# 02_POWER.net
KiCad netlist of a schematic drawn in Altium Designer
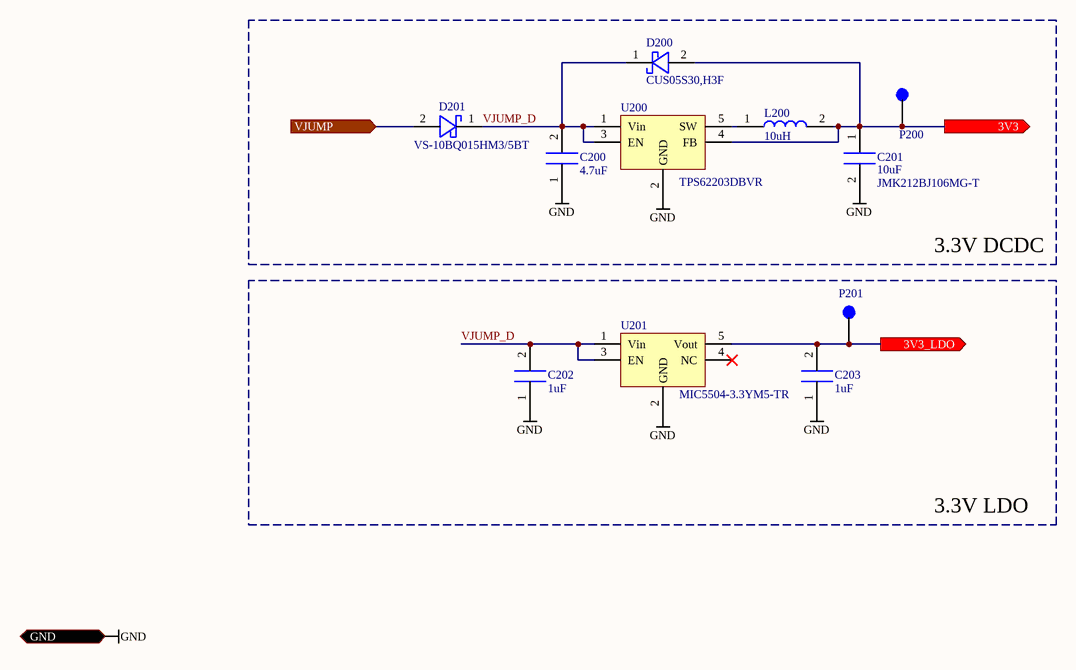
[diagram p0: 02_POWER.SchDoc]

(export (version "E")
  (design (tool "Eeschema 10.0.6"))
  (components
    (comp (ref "C200")
      (value "4.7uF")
      (footprint "CAP_0805")
      (description "CAP 4.7uF 10% 16V 0805 X7R")
      (fields (field (name "TOLERANCE") "10%") (field (name "MANUFACTURER") "MURATA"))
      (libsource (lib "Capacitors") (part "4.7uF_10%_16V_0805_X7R_GRM21BR71C475KE51L"))
    )
    (comp (ref "C201")
      (value "10uF")
      (footprint "CAP_0805")
      (description "CAP 10uF 20% 6.3V 0805 X5R")
      (fields
        (field (name "TOLERANCE") "20%")
        (field (name "MANUFACTURER") "TAYIO YUDEN")
        (field (name "MANUFACTURER REFERENCE") "JMK212BJ106MG-T")
      )
      (libsource (lib "Capacitors") (part "10uF_20%_6.3V_0805_X5R_JMK212BJ106MG-T"))
    )
    (comp (ref "C202")
      (value "1uF")
      (footprint "CAP_0402")
      (description "CAPACITOR 1uF 10% X5R 0402")
      (fields (field (name "TOLERANCE") "10%") (field (name "MANUFACTURER") "MURATA"))
      (libsource (lib "Capacitors") (part "1uF_10%_35V_0402_GRM155R6YA105KE11J"))
    )
    (comp (ref "C203")
      (value "1uF")
      (footprint "CAP_0402")
      (description "CAPACITOR 1uF 10% X5R 0402")
      (fields (field (name "TOLERANCE") "10%") (field (name "MANUFACTURER") "MURATA"))
      (libsource (lib "Capacitors") (part "1uF_10%_35V_0402_GRM155R6YA105KE11J"))
    )
    (comp (ref "D200")
      (value "DIODE_30V_500mA_340mVf_CUS05S30,H3F")
      (footprint "SOD-323")
      (description "DIODE 30V 500mA 340mVf CUS05S30,H3F")
      (fields (field (name "MANUFACTURER") "TOSHIBA") (field (name "MANUFACTURER REFERENCE") "CUS05S30,H3F"))
      (libsource (lib "Semiconductor") (part "DIODE_30V_500mA_340mVf_CUS05S30,H3F"))
    )
    (comp (ref "D201")
      (value "DIODE_15V_1A_210mVf_VS-10BQ015HM3/5BT")
      (footprint "DO-214AA")
      (description "DIODE 15V 1A 210mVf VS-10BQ015HM3/5BT")
      (fields
        (field (name "MANUFACTURER") "VISHAY")
        (field (name "MANUFACTURER REFERENCE") "VS-10BQ015HM3/5BT")
      )
      (libsource (lib "Semiconductor") (part "DIODE_15V_1A_210mVf_VS-10BQ015HM3/5BT"))
    )
    (comp (ref "L200")
      (value "10uH")
      (footprint "IND_CDRH5D28")
      (description "INDUCTOR 10uH 30% 1.3A CDRH5D28-100NC")
      (fields (field (name "TOLERANCE") "30%") (field (name "MANUFACTURER") "SUMIDA"))
      (libsource (lib "Inductors") (part "10uH_30%_1.3A_CDRH5D28-100NC"))
    )
    (comp (ref "P200")
      (value "TEST_POINT_2mm")
      (footprint "TEST_POINT_2mm")
      (libsource (lib "Connectors") (part "TEST_POINT_2mm"))
    )
    (comp (ref "P201")
      (value "TEST_POINT_2mm")
      (footprint "TEST_POINT_2mm")
      (libsource (lib "Connectors") (part "TEST_POINT_2mm"))
    )
    (comp (ref "U200")
      (value "DCDC_6VIN_3.3VOUT_600mA_TPS62203DBVR")
      (footprint "SC-74A-5 SOT-23-5")
      (description "DCDC 2-5Vin 3.3Vout 1A 300mA TPS62203DBVR")
      (fields (field (name "MANUFACTURER") "TI") (field (name "MANUFACTURER REFERENCE") "TPS62203DBVR"))
      (libsource (lib "Semiconductor") (part "DCDC_5VIN_3.3VOUT_1A_TPS62203DBVR"))
    )
    (comp (ref "U201")
      (value "LDO_6Vin_3.3Vout_MIC5504-3.3YM5-TR")
      (footprint "SC-74A-5 SOT-23-5")
      (description "LDO 6Vin 3.3Vout MIC5504-3.3YM5-TR")
      (fields
        (field (name "MANUFACTURER") "MICROCHIP")
        (field (name "MANUFACTURER REFERENCE") "MIC5504-3.3YM5-TR")
      )
      (libsource (lib "Semiconductor") (part "LDO_6Vin_3.3Vout_MIC5504-3.3YM5-TR"))
    )
  )
  (nets
    (net (code "1") (name "/3V3") (class "Default")
      (node (ref "C201") (pin "1") (pinfunction "1_1") (pintype "passive"))
      (node (ref "D200") (pin "2") (pinfunction "2_2") (pintype "passive"))
      (node (ref "L200") (pin "2") (pinfunction "2_2") (pintype "passive"))
      (node (ref "P200") (pin "1") (pinfunction "1_1") (pintype "passive"))
      (node (ref "U200") (pin "4") (pinfunction "FB_4") (pintype "passive"))
    )
    (net (code "2") (name "/3V3_LDO") (class "Default")
      (node (ref "C203") (pin "2") (pinfunction "2_2") (pintype "passive"))
      (node (ref "P201") (pin "1") (pinfunction "1_1") (pintype "passive"))
      (node (ref "U201") (pin "5") (pinfunction "Vout_5") (pintype "passive"))
    )
    (net (code "3") (name "/VJUMP") (class "Default")
      (node (ref "D201") (pin "2") (pinfunction "2_2") (pintype "passive"))
    )
    (net (code "4") (name "/VJUMP_D") (class "Default")
      (node (ref "C200") (pin "2") (pinfunction "2_2") (pintype "passive"))
      (node (ref "C202") (pin "2") (pinfunction "2_2") (pintype "passive"))
      (node (ref "D200") (pin "1") (pinfunction "1_1") (pintype "passive"))
      (node (ref "D201") (pin "1") (pinfunction "1_1") (pintype "passive"))
      (node (ref "U200") (pin "1") (pinfunction "Vin_1") (pintype "passive"))
      (node (ref "U200") (pin "3") (pinfunction "EN_3") (pintype "passive"))
      (node (ref "U201") (pin "1") (pinfunction "Vin_1") (pintype "passive"))
      (node (ref "U201") (pin "3") (pinfunction "EN_3") (pintype "passive"))
    )
    (net (code "5") (name "GND") (class "Default")
      (node (ref "C200") (pin "1") (pinfunction "1_1") (pintype "passive"))
      (node (ref "C201") (pin "2") (pinfunction "2_2") (pintype "passive"))
      (node (ref "C202") (pin "1") (pinfunction "1_1") (pintype "passive"))
      (node (ref "C203") (pin "1") (pinfunction "1_1") (pintype "passive"))
      (node (ref "U200") (pin "2") (pinfunction "GND_2") (pintype "passive"))
      (node (ref "U201") (pin "2") (pinfunction "GND_2") (pintype "passive"))
    )
    (net (code "6") (name "Net-(U200-SW)") (class "Default")
      (node (ref "L200") (pin "1") (pinfunction "1_1") (pintype "passive"))
      (node (ref "U200") (pin "5") (pinfunction "SW_5") (pintype "passive"))
    )
    (net (code "7") (name "unconnected-(U201-NC-Pad4)") (class "Default")
      (node (ref "U201") (pin "4") (pinfunction "NC_4") (pintype "passive+no_connect"))
    )
  )
)
